# Fortuna.net
KiCad netlist of a schematic drawn in EAGLE
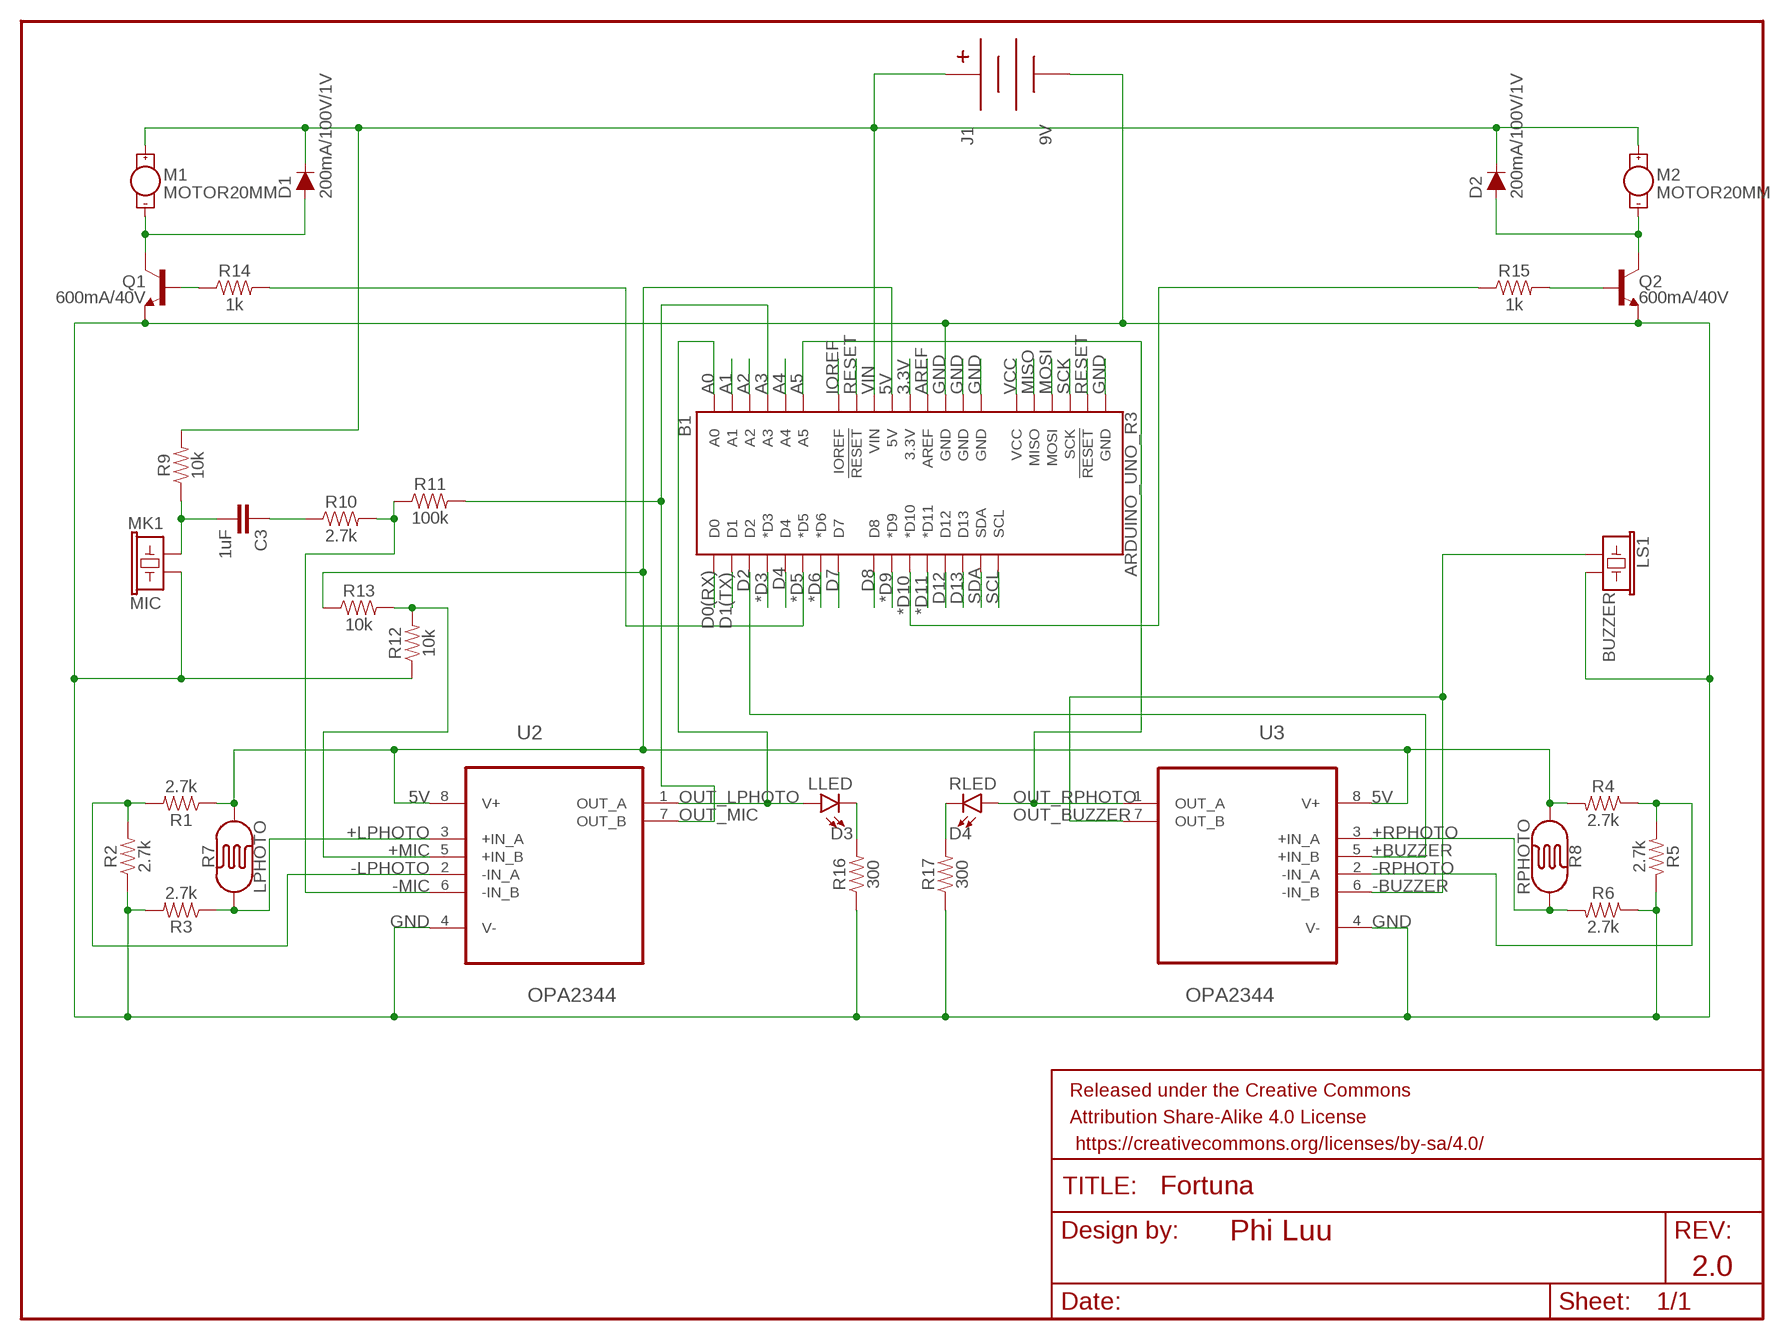
[diagram p0: schematic, sheet 1]

(export (version "E")
  (design (tool "Eeschema 10.0.6"))
  (components
    (comp (ref "B1")
      (value "ARDUINO_UNO_R3")
      (footprint "eagle-import:ARDUINO_R3")
      (libsource (lib "eagle-import") (part "ARDUINO_UNO_R3"))
    )
    (comp (ref "C3")
      (value "1uF")
      (footprint "eagle-import:CAP-PTH-SMALL-KIT")
      (libsource (lib "eagle-import") (part "0.1UF-KIT-EZ-50V-20%"))
    )
    (comp (ref "D1")
      (value "200mA/100V/1V")
      (footprint "eagle-import:DIODE-1N4148")
      (libsource (lib "eagle-import") (part "DIODE-1N4148"))
    )
    (comp (ref "D2")
      (value "200mA/100V/1V")
      (footprint "eagle-import:DIODE-1N4148")
      (libsource (lib "eagle-import") (part "DIODE-1N4148"))
    )
    (comp (ref "D3")
      (value "LLED")
      (footprint "eagle-import:LED_3MM")
      (libsource (lib "eagle-import") (part "LED3MM"))
    )
    (comp (ref "D4")
      (value "RLED")
      (footprint "eagle-import:LED_3MM")
      (libsource (lib "eagle-import") (part "LED3MM"))
    )
    (comp (ref "FRAME1")
      (value "FRAME-LETTER")
      (footprint "eagle-import:CREATIVE_COMMONS")
      (libsource (lib "eagle-import") (part "FRAME-LETTER"))
    )
    (comp (ref "J1")
      (value "9V")
      (footprint "eagle-import:BC9VPC")
      (libsource (lib "eagle-import") (part "BC9VPC"))
    )
    (comp (ref "LS1")
      (value "BUZZER")
      (footprint "eagle-import:BUZZER-12MM")
      (libsource (lib "eagle-import") (part "BUZZER-PTH"))
    )
    (comp (ref "M1")
      (value "MOTOR20MM")
      (footprint "eagle-import:VIBE-MOTOR-10MM")
      (libsource (lib "eagle-import") (part "MOTOR10MM"))
    )
    (comp (ref "M2")
      (value "MOTOR20MM")
      (footprint "eagle-import:VIBE-MOTOR-10MM")
      (libsource (lib "eagle-import") (part "MOTOR10MM"))
    )
    (comp (ref "MK1")
      (value "MIC")
      (footprint "eagle-import:MICROPHONE-PTH-9.7MM")
      (libsource (lib "eagle-import") (part "MIC-PTH"))
    )
    (comp (ref "Q1")
      (value "600mA/40V")
      (footprint "eagle-import:TO-92")
      (libsource (lib "eagle-import") (part "TRANS_NPN-P2N2222A"))
    )
    (comp (ref "Q2")
      (value "600mA/40V")
      (footprint "eagle-import:TO-92")
      (libsource (lib "eagle-import") (part "TRANS_NPN-P2N2222A"))
    )
    (comp (ref "R1")
      (value "2.7k")
      (footprint "eagle-import:AXIAL-0.3")
      (libsource (lib "eagle-import") (part "1KOHM-HORIZ-1/4W-5%"))
    )
    (comp (ref "R2")
      (value "2.7k")
      (footprint "eagle-import:AXIAL-0.3")
      (libsource (lib "eagle-import") (part "1KOHM-HORIZ-1/4W-5%"))
    )
    (comp (ref "R3")
      (value "2.7k")
      (footprint "eagle-import:AXIAL-0.3")
      (libsource (lib "eagle-import") (part "1KOHM-HORIZ-1/4W-5%"))
    )
    (comp (ref "R4")
      (value "2.7k")
      (footprint "eagle-import:AXIAL-0.3")
      (libsource (lib "eagle-import") (part "1KOHM-HORIZ-1/4W-5%"))
    )
    (comp (ref "R5")
      (value "2.7k")
      (footprint "eagle-import:AXIAL-0.3")
      (libsource (lib "eagle-import") (part "1KOHM-HORIZ-1/4W-5%"))
    )
    (comp (ref "R6")
      (value "2.7k")
      (footprint "eagle-import:AXIAL-0.3")
      (libsource (lib "eagle-import") (part "1KOHM-HORIZ-1/4W-5%"))
    )
    (comp (ref "R7")
      (value "LPHOTO")
      (footprint "eagle-import:PHOTOCELL")
      (libsource (lib "eagle-import") (part "PHOTOCELLPTH"))
    )
    (comp (ref "R8")
      (value "RPHOTO")
      (footprint "eagle-import:PHOTOCELL")
      (libsource (lib "eagle-import") (part "PHOTOCELLPTH"))
    )
    (comp (ref "R9")
      (value "10k")
      (footprint "eagle-import:AXIAL-0.3")
      (libsource (lib "eagle-import") (part "1KOHM-HORIZ-1/4W-5%"))
    )
    (comp (ref "R10")
      (value "2.7k")
      (footprint "eagle-import:AXIAL-0.3")
      (libsource (lib "eagle-import") (part "1KOHM-HORIZ-1/4W-5%"))
    )
    (comp (ref "R11")
      (value "100k")
      (footprint "eagle-import:AXIAL-0.3")
      (libsource (lib "eagle-import") (part "1KOHM-HORIZ-1/4W-5%"))
    )
    (comp (ref "R12")
      (value "10k")
      (footprint "eagle-import:AXIAL-0.3")
      (libsource (lib "eagle-import") (part "1KOHM-HORIZ-1/4W-5%"))
    )
    (comp (ref "R13")
      (value "10k")
      (footprint "eagle-import:AXIAL-0.3")
      (libsource (lib "eagle-import") (part "1KOHM-HORIZ-1/4W-5%"))
    )
    (comp (ref "R14")
      (value "1k")
      (footprint "eagle-import:AXIAL-0.3")
      (libsource (lib "eagle-import") (part "1KOHM-HORIZ-1/4W-5%"))
    )
    (comp (ref "R15")
      (value "1k")
      (footprint "eagle-import:AXIAL-0.3")
      (libsource (lib "eagle-import") (part "1KOHM-HORIZ-1/4W-5%"))
    )
    (comp (ref "R16")
      (value "300")
      (footprint "eagle-import:AXIAL-0.3")
      (libsource (lib "eagle-import") (part "1KOHM-HORIZ-1/4W-5%"))
    )
    (comp (ref "R17")
      (value "300")
      (footprint "eagle-import:AXIAL-0.3")
      (libsource (lib "eagle-import") (part "1KOHM-HORIZ-1/4W-5%"))
    )
    (comp (ref "U2")
      (value "OPA2344")
      (footprint "eagle-import:SOIC127P600X175-8N")
      (fields (field (name "MPN") "OPA2343UA"))
      (libsource (lib "eagle-import") (part "OPA2343UA"))
    )
    (comp (ref "U3")
      (value "OPA2344")
      (footprint "eagle-import:SOIC127P600X175-8N")
      (fields (field (name "MPN") "OPA2343UA"))
      (libsource (lib "eagle-import") (part "OPA2343UA"))
    )
  )
  (nets
    (net (code "1") (name "/*D3") (class "Default")
      (node (ref "B1") (pin "D3") (pinfunction "*D3_D3") (pintype "bidirectional"))
    )
    (net (code "2") (name "/*D5") (class "Default")
      (node (ref "B1") (pin "D5") (pinfunction "*D5_D5") (pintype "bidirectional"))
      (node (ref "R14") (pin "P$2") (pinfunction "2_P$2") (pintype "passive"))
    )
    (net (code "3") (name "/*D6") (class "Default")
      (node (ref "B1") (pin "D6") (pinfunction "*D6_D6") (pintype "bidirectional"))
    )
    (net (code "4") (name "/*D9") (class "Default")
      (node (ref "B1") (pin "D9") (pinfunction "*D9_D9") (pintype "bidirectional"))
    )
    (net (code "5") (name "/*D10") (class "Default")
      (node (ref "B1") (pin "D10") (pinfunction "*D10_D10") (pintype "bidirectional"))
      (node (ref "R15") (pin "P$1") (pinfunction "1_P$1") (pintype "passive"))
    )
    (net (code "6") (name "/*D11") (class "Default")
      (node (ref "B1") (pin "D11") (pinfunction "*D11_D11") (pintype "bidirectional"))
    )
    (net (code "7") (name "/+LPHOTO") (class "Default")
      (node (ref "R3") (pin "P$1") (pinfunction "1_P$1") (pintype "passive"))
      (node (ref "R7") (pin "1") (pinfunction "P$1_1") (pintype "bidirectional"))
      (node (ref "U2") (pin "3") (pinfunction "+IN_A_3") (pintype "input"))
    )
    (net (code "8") (name "/+MIC") (class "Default")
      (node (ref "R12") (pin "P$2") (pinfunction "2_P$2") (pintype "passive"))
      (node (ref "R13") (pin "P$2") (pinfunction "2_P$2") (pintype "passive"))
      (node (ref "U2") (pin "5") (pinfunction "+IN_B_5") (pintype "input"))
    )
    (net (code "9") (name "/+RPHOTO") (class "Default")
      (node (ref "R6") (pin "P$2") (pinfunction "2_P$2") (pintype "passive"))
      (node (ref "R8") (pin "1") (pinfunction "P$1_1") (pintype "bidirectional"))
      (node (ref "U3") (pin "3") (pinfunction "+IN_A_3") (pintype "input"))
    )
    (net (code "10") (name "/-LPHOTO") (class "Default")
      (node (ref "R1") (pin "P$2") (pinfunction "2_P$2") (pintype "passive"))
      (node (ref "R2") (pin "P$2") (pinfunction "2_P$2") (pintype "passive"))
      (node (ref "U2") (pin "2") (pinfunction "-IN_A_2") (pintype "input"))
    )
    (net (code "11") (name "/-MIC") (class "Default")
      (node (ref "R10") (pin "P$2") (pinfunction "2_P$2") (pintype "passive"))
      (node (ref "R11") (pin "P$1") (pinfunction "1_P$1") (pintype "passive"))
      (node (ref "U2") (pin "6") (pinfunction "-IN_B_6") (pintype "input"))
    )
    (net (code "12") (name "/-RPHOTO") (class "Default")
      (node (ref "R4") (pin "P$1") (pinfunction "1_P$1") (pintype "passive"))
      (node (ref "R5") (pin "P$2") (pinfunction "2_P$2") (pintype "passive"))
      (node (ref "U3") (pin "2") (pinfunction "-IN_A_2") (pintype "input"))
    )
    (net (code "13") (name "/3.3V") (class "Default")
      (node (ref "B1") (pin "3.3V") (pinfunction "3.3V_3.3V") (pintype "bidirectional"))
    )
    (net (code "14") (name "/5V") (class "Default")
      (node (ref "B1") (pin "5V") (pinfunction "5V_5V") (pintype "bidirectional"))
      (node (ref "R1") (pin "P$1") (pinfunction "1_P$1") (pintype "passive"))
      (node (ref "R13") (pin "P$1") (pinfunction "1_P$1") (pintype "passive"))
      (node (ref "R4") (pin "P$2") (pinfunction "2_P$2") (pintype "passive"))
      (node (ref "R7") (pin "2") (pinfunction "P$2_2") (pintype "bidirectional"))
      (node (ref "R8") (pin "2") (pinfunction "P$2_2") (pintype "bidirectional"))
      (node (ref "U2") (pin "8") (pinfunction "V+_8") (pintype "power_in"))
      (node (ref "U3") (pin "8") (pinfunction "V+_8") (pintype "power_in"))
    )
    (net (code "15") (name "/A0") (class "Default")
      (node (ref "B1") (pin "A0") (pinfunction "A0_A0") (pintype "bidirectional"))
      (node (ref "D3") (pin "A") (pinfunction "A_A") (pintype "passive"))
      (node (ref "U2") (pin "1") (pinfunction "OUT_A_1") (pintype "output"))
    )
    (net (code "16") (name "/A1") (class "Default")
      (node (ref "B1") (pin "A1") (pinfunction "A1_A1") (pintype "bidirectional"))
    )
    (net (code "17") (name "/A2") (class "Default")
      (node (ref "B1") (pin "A2") (pinfunction "A2_A2") (pintype "bidirectional"))
    )
    (net (code "18") (name "/A3") (class "Default")
      (node (ref "B1") (pin "A3") (pinfunction "A3_A3") (pintype "bidirectional"))
      (node (ref "R11") (pin "P$2") (pinfunction "2_P$2") (pintype "passive"))
      (node (ref "U2") (pin "7") (pinfunction "OUT_B_7") (pintype "output"))
    )
    (net (code "19") (name "/A4") (class "Default")
      (node (ref "B1") (pin "A4") (pinfunction "A4_A4") (pintype "bidirectional"))
    )
    (net (code "20") (name "/A5") (class "Default")
      (node (ref "B1") (pin "A5") (pinfunction "A5_A5") (pintype "bidirectional"))
      (node (ref "D4") (pin "A") (pinfunction "A_A") (pintype "passive"))
      (node (ref "U3") (pin "1") (pinfunction "OUT_A_1") (pintype "output"))
    )
    (net (code "21") (name "/AREF") (class "Default")
      (node (ref "B1") (pin "AREF") (pinfunction "AREF_AREF") (pintype "bidirectional"))
    )
    (net (code "22") (name "/D0(RX)") (class "Default")
      (node (ref "B1") (pin "D0") (pinfunction "D0_D0") (pintype "bidirectional"))
    )
    (net (code "23") (name "/D1(TX)") (class "Default")
      (node (ref "B1") (pin "D1") (pinfunction "D1_D1") (pintype "bidirectional"))
    )
    (net (code "24") (name "/D2") (class "Default")
      (node (ref "B1") (pin "D2") (pinfunction "D2_D2") (pintype "bidirectional"))
      (node (ref "U3") (pin "5") (pinfunction "+IN_B_5") (pintype "input"))
    )
    (net (code "25") (name "/D4") (class "Default")
      (node (ref "B1") (pin "D4") (pinfunction "D4_D4") (pintype "bidirectional"))
    )
    (net (code "26") (name "/D7") (class "Default")
      (node (ref "B1") (pin "D7") (pinfunction "D7_D7") (pintype "bidirectional"))
    )
    (net (code "27") (name "/D8") (class "Default")
      (node (ref "B1") (pin "D8") (pinfunction "D8_D8") (pintype "bidirectional"))
    )
    (net (code "28") (name "/D12") (class "Default")
      (node (ref "B1") (pin "D12") (pinfunction "D12_D12") (pintype "bidirectional"))
    )
    (net (code "29") (name "/D13") (class "Default")
      (node (ref "B1") (pin "D13") (pinfunction "D13_D13") (pintype "bidirectional"))
    )
    (net (code "30") (name "/GND") (class "Default")
      (node (ref "B1") (pin "GND@1") (pinfunction "GND_GND@1") (pintype "bidirectional"))
      (node (ref "B1") (pin "GND@2") (pinfunction "GND_GND@2") (pintype "bidirectional"))
      (node (ref "B1") (pin "GND@3") (pinfunction "GND_GND@3") (pintype "bidirectional"))
      (node (ref "B1") (pin "GND@4") (pinfunction "GND_GND@4") (pintype "bidirectional"))
      (node (ref "J1") (pin "V-") (pinfunction "V-_V-") (pintype "bidirectional"))
      (node (ref "LS1") (pin "-") (pinfunction "2_-") (pintype "passive"))
      (node (ref "MK1") (pin "GND") (pinfunction "2_GND") (pintype "passive"))
      (node (ref "Q1") (pin "3") (pinfunction "E_3") (pintype "passive"))
      (node (ref "Q2") (pin "3") (pinfunction "E_3") (pintype "passive"))
      (node (ref "R12") (pin "P$1") (pinfunction "1_P$1") (pintype "passive"))
      (node (ref "R16") (pin "P$1") (pinfunction "1_P$1") (pintype "passive"))
      (node (ref "R17") (pin "P$1") (pinfunction "1_P$1") (pintype "passive"))
      (node (ref "R2") (pin "P$1") (pinfunction "1_P$1") (pintype "passive"))
      (node (ref "R3") (pin "P$2") (pinfunction "2_P$2") (pintype "passive"))
      (node (ref "R5") (pin "P$1") (pinfunction "1_P$1") (pintype "passive"))
      (node (ref "R6") (pin "P$1") (pinfunction "1_P$1") (pintype "passive"))
      (node (ref "U2") (pin "4") (pinfunction "V-_4") (pintype "power_in"))
      (node (ref "U3") (pin "4") (pinfunction "V-_4") (pintype "power_in"))
    )
    (net (code "31") (name "/IOREF") (class "Default")
      (node (ref "B1") (pin "IOREF") (pinfunction "IOREF_IOREF") (pintype "bidirectional"))
    )
    (net (code "32") (name "/MISO") (class "Default")
      (node (ref "B1") (pin "MISO") (pinfunction "MISO_MISO") (pintype "bidirectional"))
    )
    (net (code "33") (name "/MOSI") (class "Default")
      (node (ref "B1") (pin "MOSI") (pinfunction "MOSI_MOSI") (pintype "bidirectional"))
    )
    (net (code "34") (name "/OUT_BUZZER") (class "Default")
      (node (ref "LS1") (pin "+") (pinfunction "1_+") (pintype "passive"))
      (node (ref "U3") (pin "6") (pinfunction "-IN_B_6") (pintype "input"))
      (node (ref "U3") (pin "7") (pinfunction "OUT_B_7") (pintype "output"))
    )
    (net (code "35") (name "/RESET") (class "Default")
      (node (ref "B1") (pin "RESET@1") (pinfunction "~{RESET}_RESET@1") (pintype "bidirectional"))
      (node (ref "B1") (pin "RESET@2") (pinfunction "~{RESET}_RESET@2") (pintype "bidirectional"))
    )
    (net (code "36") (name "/SCK") (class "Default")
      (node (ref "B1") (pin "SCK") (pinfunction "SCK_SCK") (pintype "bidirectional"))
    )
    (net (code "37") (name "/SCL") (class "Default")
      (node (ref "B1") (pin "SCL") (pinfunction "SCL_SCL") (pintype "bidirectional"))
    )
    (net (code "38") (name "/SDA") (class "Default")
      (node (ref "B1") (pin "SDA") (pinfunction "SDA_SDA") (pintype "bidirectional"))
    )
    (net (code "39") (name "/VCC") (class "Default")
      (node (ref "B1") (pin "VCC") (pinfunction "VCC_VCC") (pintype "bidirectional"))
    )
    (net (code "40") (name "/VIN") (class "Default")
      (node (ref "B1") (pin "VIN") (pinfunction "VIN_VIN") (pintype "bidirectional"))
      (node (ref "D1") (pin "C") (pinfunction "C_C") (pintype "passive"))
      (node (ref "D2") (pin "C") (pinfunction "C_C") (pintype "passive"))
      (node (ref "J1") (pin "V+") (pinfunction "V+_V+") (pintype "bidirectional"))
      (node (ref "M1") (pin "+") (pinfunction "+_+") (pintype "bidirectional"))
      (node (ref "M2") (pin "+") (pinfunction "+_+") (pintype "bidirectional"))
      (node (ref "R9") (pin "P$2") (pinfunction "2_P$2") (pintype "passive"))
    )
    (net (code "41") (name "Net-(D3-C)") (class "Default")
      (node (ref "D3") (pin "K") (pinfunction "C_K") (pintype "passive"))
      (node (ref "R16") (pin "P$2") (pinfunction "2_P$2") (pintype "passive"))
    )
    (net (code "42") (name "Net-(D4-C)") (class "Default")
      (node (ref "D4") (pin "K") (pinfunction "C_K") (pintype "passive"))
      (node (ref "R17") (pin "P$2") (pinfunction "2_P$2") (pintype "passive"))
    )
    (net (code "43") (name "Net-(MK1-1)") (class "Default")
      (node (ref "C3") (pin "2") (pinfunction "2_2") (pintype "passive"))
      (node (ref "MK1") (pin "OUT") (pinfunction "1_OUT") (pintype "passive"))
      (node (ref "R9") (pin "P$1") (pinfunction "1_P$1") (pintype "passive"))
    )
    (net (code "44") (name "Net-(Q1-B)") (class "Default")
      (node (ref "Q1") (pin "2") (pinfunction "B_2") (pintype "passive"))
      (node (ref "R14") (pin "P$1") (pinfunction "1_P$1") (pintype "passive"))
    )
    (net (code "45") (name "Net-(Q1-C)") (class "Default")
      (node (ref "D1") (pin "A") (pinfunction "A_A") (pintype "passive"))
      (node (ref "M1") (pin "-") (pinfunction "-_-") (pintype "bidirectional"))
      (node (ref "Q1") (pin "1") (pinfunction "C_1") (pintype "passive"))
    )
    (net (code "46") (name "Net-(Q2-B)") (class "Default")
      (node (ref "Q2") (pin "2") (pinfunction "B_2") (pintype "passive"))
      (node (ref "R15") (pin "P$2") (pinfunction "2_P$2") (pintype "passive"))
    )
    (net (code "47") (name "Net-(Q2-C)") (class "Default")
      (node (ref "D2") (pin "A") (pinfunction "A_A") (pintype "passive"))
      (node (ref "M2") (pin "-") (pinfunction "-_-") (pintype "bidirectional"))
      (node (ref "Q2") (pin "1") (pinfunction "C_1") (pintype "passive"))
    )
    (net (code "48") (name "Net-(R10-1)") (class "Default")
      (node (ref "C3") (pin "1") (pinfunction "1_1") (pintype "passive"))
      (node (ref "R10") (pin "P$1") (pinfunction "1_P$1") (pintype "passive"))
    )
  )
)
